# AD.net
KiCad netlist of a schematic drawn in Altium Designer
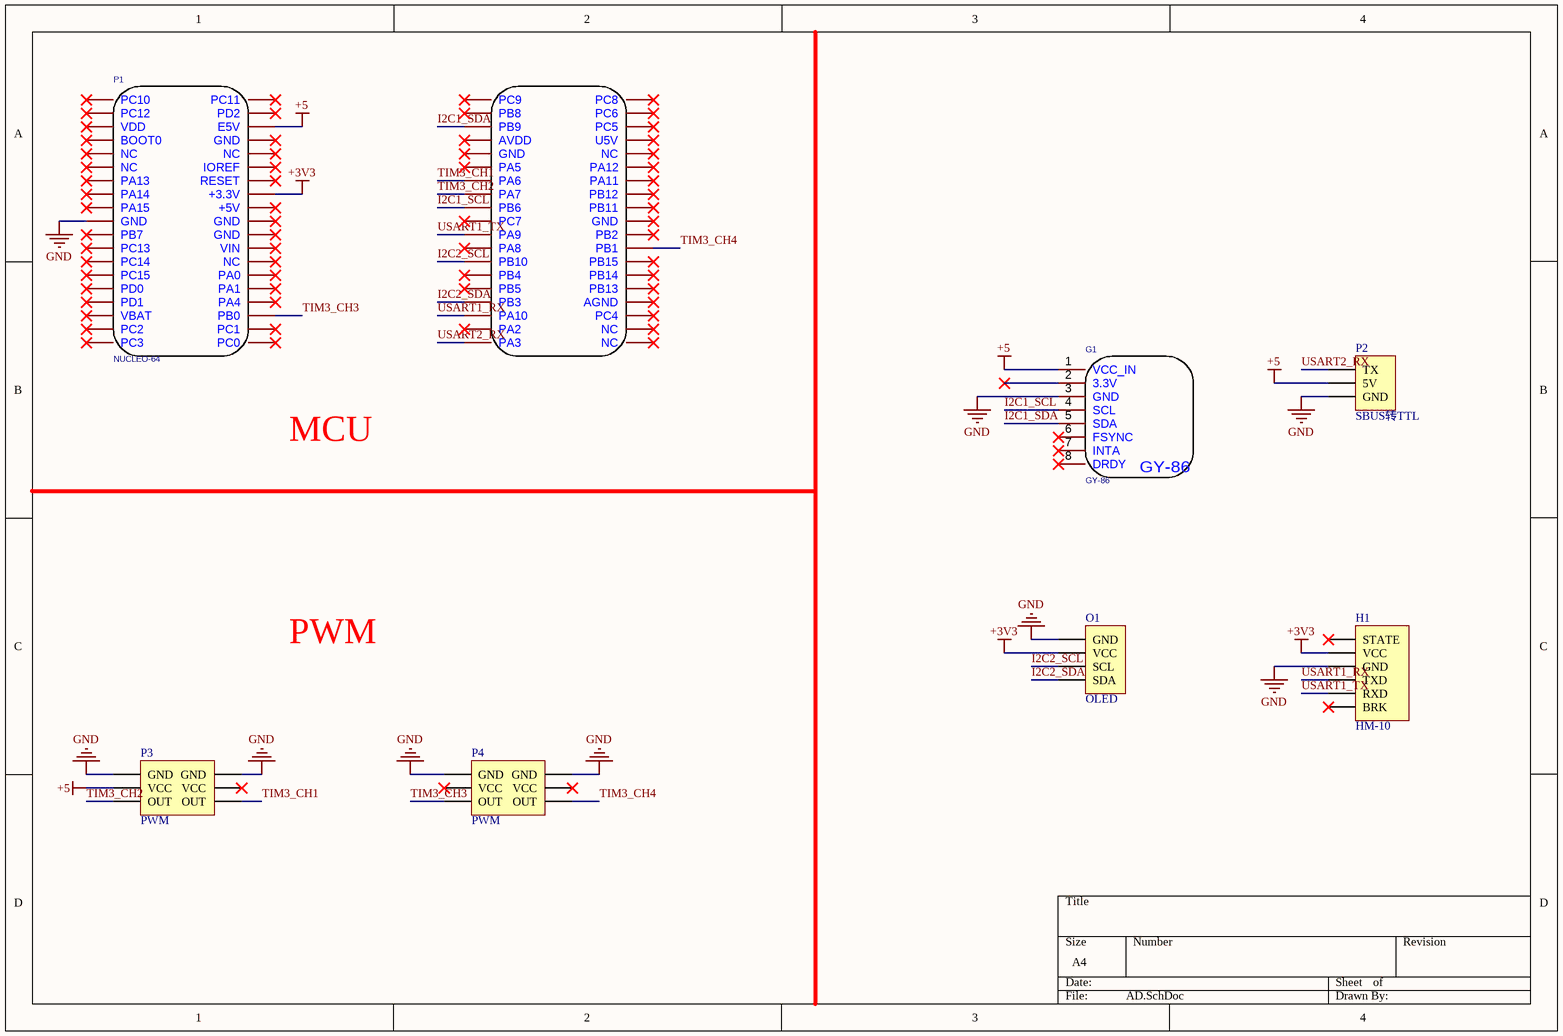
[diagram p0: AD.SchDoc]

(export (version "E")
  (design (tool "Eeschema 10.0.6"))
  (components
    (comp (ref "G1")
      (value "GY-86")
      (footprint "GY-86")
      (description "GY-86模块")
      (libsource (lib "AD") (part "GY-86"))
    )
    (comp (ref "H1")
      (value "HM-10")
      (footprint "HDR1X6")
      (description "HM-10蓝牙模块")
      (fields (field (name "PUBLISHER") "Altium Limited"))
      (libsource (lib "AD") (part "HM-10"))
    )
    (comp (ref "O1")
      (value "OLED")
      (footprint "HDR1X4")
      (description "使用I2C通信的0.96寸OLED模块")
      (fields (field (name "PUBLISHER") "Altium Limited"))
      (libsource (lib "AD") (part "OLED"))
    )
    (comp (ref "P1")
      (value "NUCLEO-64")
      (footprint "NUCLEO-F103RB")
      (description "STM32F401NUCLEO开发板")
      (fields (field (name "MANUFACTURER") "ST"))
      (libsource (lib "AD") (part "NUCLEO-64"))
    )
    (comp (ref "P2")
      (value "SBUS转TTL")
      (footprint "HDR1X3")
      (description "SBUS转TTL模块")
      (fields (field (name "PUBLISHER") "Altium Limited"))
      (libsource (lib "AD") (part "SBUS转TTL"))
    )
    (comp (ref "P3")
      (value "PWM")
      (footprint "HDR2.54-WI-2x3P")
      (description "电机PWM输出")
      (fields (field (name "PUBLISHER") "Altium Limited"))
      (libsource (lib "AD") (part "PWM"))
    )
    (comp (ref "P4")
      (value "PWM")
      (footprint "HDR2.54-WI-2x3P")
      (description "电机PWM输出")
      (fields (field (name "PUBLISHER") "Altium Limited"))
      (libsource (lib "AD") (part "PWM"))
    )
  )
  (nets
    (net (code "1") (name "+3V3") (class "Default")
      (node (ref "H1") (pin "2") (pinfunction "VCC_2") (pintype "passive"))
      (node (ref "O1") (pin "2") (pinfunction "VCC_2") (pintype "passive"))
      (node (ref "P1") (pin "16") (pinfunction "+3.3V_16") (pintype "passive"))
    )
    (net (code "2") (name "+5") (class "Default")
      (node (ref "G1") (pin "1") (pinfunction "VCC_IN_1") (pintype "passive"))
      (node (ref "P1") (pin "6") (pinfunction "E5V_6") (pintype "passive"))
      (node (ref "P2") (pin "2") (pinfunction "5V_2") (pintype "passive"))
      (node (ref "P3") (pin "3") (pinfunction "VCC_3") (pintype "passive"))
    )
    (net (code "3") (name "/I2C1_SCL") (class "Default")
      (node (ref "G1") (pin "4") (pinfunction "SCL_4") (pintype "passive"))
      (node (ref "P1") (pin "89") (pinfunction "PB6_89") (pintype "passive"))
    )
    (net (code "4") (name "/I2C1_SDA") (class "Default")
      (node (ref "G1") (pin "5") (pinfunction "SDA_5") (pintype "passive"))
      (node (ref "P1") (pin "77") (pinfunction "PB9_77") (pintype "passive"))
    )
    (net (code "5") (name "/I2C2_SCL") (class "Default")
      (node (ref "O1") (pin "3") (pinfunction "SCL_3") (pintype "passive"))
      (node (ref "P1") (pin "97") (pinfunction "PB10_97") (pintype "passive"))
    )
    (net (code "6") (name "/I2C2_SDA") (class "Default")
      (node (ref "O1") (pin "4") (pinfunction "SDA_4") (pintype "passive"))
      (node (ref "P1") (pin "103") (pinfunction "PB3_103") (pintype "passive"))
    )
    (net (code "7") (name "/TIM3_CH1") (class "Default")
      (node (ref "P1") (pin "85") (pinfunction "PA6_85") (pintype "passive"))
      (node (ref "P3") (pin "6") (pinfunction "OUT_6") (pintype "passive"))
    )
    (net (code "8") (name "/TIM3_CH2") (class "Default")
      (node (ref "P1") (pin "87") (pinfunction "PA7_87") (pintype "passive"))
      (node (ref "P3") (pin "5") (pinfunction "OUT_5") (pintype "passive"))
    )
    (net (code "9") (name "/TIM3_CH3") (class "Default")
      (node (ref "P1") (pin "34") (pinfunction "PB0_34") (pintype "passive"))
      (node (ref "P4") (pin "5") (pinfunction "OUT_5") (pintype "passive"))
    )
    (net (code "10") (name "/TIM3_CH4") (class "Default")
      (node (ref "P1") (pin "96") (pinfunction "PB1_96") (pintype "passive"))
      (node (ref "P4") (pin "6") (pinfunction "OUT_6") (pintype "passive"))
    )
    (net (code "11") (name "/USART1_RX") (class "Default")
      (node (ref "H1") (pin "4") (pinfunction "TXD_4") (pintype "passive"))
      (node (ref "P1") (pin "105") (pinfunction "PA10_105") (pintype "passive"))
    )
    (net (code "12") (name "/USART1_TX") (class "Default")
      (node (ref "H1") (pin "5") (pinfunction "RXD_5") (pintype "passive"))
      (node (ref "P1") (pin "93") (pinfunction "PA9_93") (pintype "passive"))
    )
    (net (code "13") (name "/USART2_RX") (class "Default")
      (node (ref "P1") (pin "109") (pinfunction "PA3_109") (pintype "passive"))
      (node (ref "P2") (pin "1") (pinfunction "TX_1") (pintype "passive"))
    )
    (net (code "14") (name "GND") (class "Default")
      (node (ref "G1") (pin "3") (pinfunction "GND_3") (pintype "passive"))
      (node (ref "H1") (pin "3") (pinfunction "GND_3") (pintype "passive"))
      (node (ref "O1") (pin "1") (pinfunction "GND_1") (pintype "passive"))
      (node (ref "P1") (pin "19") (pinfunction "GND_19") (pintype "passive"))
      (node (ref "P2") (pin "3") (pinfunction "GND_3") (pintype "passive"))
      (node (ref "P3") (pin "1") (pinfunction "GND_1") (pintype "passive"))
      (node (ref "P3") (pin "2") (pinfunction "GND_2") (pintype "passive"))
      (node (ref "P4") (pin "1") (pinfunction "GND_1") (pintype "passive"))
      (node (ref "P4") (pin "2") (pinfunction "GND_2") (pintype "passive"))
    )
    (net (code "15") (name "unconnected-(G1-3.3V-Pad2)") (class "Default")
      (node (ref "G1") (pin "2") (pinfunction "3.3V_2") (pintype "passive+no_connect"))
    )
    (net (code "16") (name "unconnected-(G1-DRDY-Pad8)") (class "Default")
      (node (ref "G1") (pin "8") (pinfunction "DRDY_8") (pintype "passive+no_connect"))
    )
    (net (code "17") (name "unconnected-(G1-FSYNC-Pad6)") (class "Default")
      (node (ref "G1") (pin "6") (pinfunction "FSYNC_6") (pintype "passive+no_connect"))
    )
    (net (code "18") (name "unconnected-(G1-INTA-Pad7)") (class "Default")
      (node (ref "G1") (pin "7") (pinfunction "INTA_7") (pintype "passive+no_connect"))
    )
    (net (code "19") (name "unconnected-(H1-BRK-Pad6)") (class "Default")
      (node (ref "H1") (pin "6") (pinfunction "BRK_6") (pintype "passive+no_connect"))
    )
    (net (code "20") (name "unconnected-(H1-STATE-Pad1)") (class "Default")
      (node (ref "H1") (pin "1") (pinfunction "STATE_1") (pintype "passive+no_connect"))
    )
    (net (code "21") (name "unconnected-(P1-+5V-Pad18)") (class "Default")
      (node (ref "P1") (pin "18") (pinfunction "+5V_18") (pintype "passive+no_connect"))
    )
    (net (code "22") (name "unconnected-(P1-AGND-Pad104)") (class "Default")
      (node (ref "P1") (pin "104") (pinfunction "AGND_104") (pintype "passive+no_connect"))
    )
    (net (code "23") (name "unconnected-(P1-AVDD-Pad79)") (class "Default")
      (node (ref "P1") (pin "79") (pinfunction "AVDD_79") (pintype "passive+no_connect"))
    )
    (net (code "24") (name "unconnected-(P1-BOOT0-Pad7)") (class "Default")
      (node (ref "P1") (pin "7") (pinfunction "BOOT0_7") (pintype "passive+no_connect"))
    )
    (net (code "25") (name "unconnected-(P1-GND-Pad8)") (class "Default")
      (node (ref "P1") (pin "8") (pinfunction "GND_8") (pintype "passive+no_connect"))
    )
    (net (code "26") (name "unconnected-(P1-GND-Pad20)") (class "Default")
      (node (ref "P1") (pin "20") (pinfunction "GND_20") (pintype "passive+no_connect"))
    )
    (net (code "27") (name "unconnected-(P1-GND-Pad22)") (class "Default")
      (node (ref "P1") (pin "22") (pinfunction "GND_22") (pintype "passive+no_connect"))
    )
    (net (code "28") (name "unconnected-(P1-GND-Pad81)") (class "Default")
      (node (ref "P1") (pin "81") (pinfunction "GND_81") (pintype "passive+no_connect"))
    )
    (net (code "29") (name "unconnected-(P1-GND-Pad92)") (class "Default")
      (node (ref "P1") (pin "92") (pinfunction "GND_92") (pintype "passive+no_connect"))
    )
    (net (code "30") (name "unconnected-(P1-IOREF-Pad12)") (class "Default")
      (node (ref "P1") (pin "12") (pinfunction "IOREF_12") (pintype "passive+no_connect"))
    )
    (net (code "31") (name "unconnected-(P1-NC-Pad9)") (class "Default")
      (node (ref "P1") (pin "9") (pinfunction "NC_9") (pintype "passive+no_connect"))
    )
    (net (code "32") (name "unconnected-(P1-NC-Pad10)") (class "Default")
      (node (ref "P1") (pin "10") (pinfunction "NC_10") (pintype "passive+no_connect"))
    )
    (net (code "33") (name "unconnected-(P1-NC-Pad11)") (class "Default")
      (node (ref "P1") (pin "11") (pinfunction "NC_11") (pintype "passive+no_connect"))
    )
    (net (code "34") (name "unconnected-(P1-NC-Pad26)") (class "Default")
      (node (ref "P1") (pin "26") (pinfunction "NC_26") (pintype "passive+no_connect"))
    )
    (net (code "35") (name "unconnected-(P1-NC-Pad82)") (class "Default")
      (node (ref "P1") (pin "82") (pinfunction "NC_82") (pintype "passive+no_connect"))
    )
    (net (code "36") (name "unconnected-(P1-NC-Pad108)") (class "Default")
      (node (ref "P1") (pin "108") (pinfunction "NC_108") (pintype "passive+no_connect"))
    )
    (net (code "37") (name "unconnected-(P1-NC-Pad110)") (class "Default")
      (node (ref "P1") (pin "110") (pinfunction "NC_110") (pintype "passive+no_connect"))
    )
    (net (code "38") (name "unconnected-(P1-PA0-Pad28)") (class "Default")
      (node (ref "P1") (pin "28") (pinfunction "PA0_28") (pintype "passive+no_connect"))
    )
    (net (code "39") (name "unconnected-(P1-PA1-Pad30)") (class "Default")
      (node (ref "P1") (pin "30") (pinfunction "PA1_30") (pintype "passive+no_connect"))
    )
    (net (code "40") (name "unconnected-(P1-PA2-Pad107)") (class "Default")
      (node (ref "P1") (pin "107") (pinfunction "PA2_107") (pintype "passive+no_connect"))
    )
    (net (code "41") (name "unconnected-(P1-PA4-Pad32)") (class "Default")
      (node (ref "P1") (pin "32") (pinfunction "PA4_32") (pintype "passive+no_connect"))
    )
    (net (code "42") (name "unconnected-(P1-PA5-Pad83)") (class "Default")
      (node (ref "P1") (pin "83") (pinfunction "PA5_83") (pintype "passive+no_connect"))
    )
    (net (code "43") (name "unconnected-(P1-PA8-Pad95)") (class "Default")
      (node (ref "P1") (pin "95") (pinfunction "PA8_95") (pintype "passive+no_connect"))
    )
    (net (code "44") (name "unconnected-(P1-PA11-Pad86)") (class "Default")
      (node (ref "P1") (pin "86") (pinfunction "PA11_86") (pintype "passive+no_connect"))
    )
    (net (code "45") (name "unconnected-(P1-PA12-Pad84)") (class "Default")
      (node (ref "P1") (pin "84") (pinfunction "PA12_84") (pintype "passive+no_connect"))
    )
    (net (code "46") (name "unconnected-(P1-PA13-Pad13)") (class "Default")
      (node (ref "P1") (pin "13") (pinfunction "PA13_13") (pintype "passive+no_connect"))
    )
    (net (code "47") (name "unconnected-(P1-PA14-Pad15)") (class "Default")
      (node (ref "P1") (pin "15") (pinfunction "PA14_15") (pintype "passive+no_connect"))
    )
    (net (code "48") (name "unconnected-(P1-PA15-Pad17)") (class "Default")
      (node (ref "P1") (pin "17") (pinfunction "PA15_17") (pintype "passive+no_connect"))
    )
    (net (code "49") (name "unconnected-(P1-PB2-Pad94)") (class "Default")
      (node (ref "P1") (pin "94") (pinfunction "PB2_94") (pintype "passive+no_connect"))
    )
    (net (code "50") (name "unconnected-(P1-PB4-Pad99)") (class "Default")
      (node (ref "P1") (pin "99") (pinfunction "PB4_99") (pintype "passive+no_connect"))
    )
    (net (code "51") (name "unconnected-(P1-PB5-Pad101)") (class "Default")
      (node (ref "P1") (pin "101") (pinfunction "PB5_101") (pintype "passive+no_connect"))
    )
    (net (code "52") (name "unconnected-(P1-PB7-Pad21)") (class "Default")
      (node (ref "P1") (pin "21") (pinfunction "PB7_21") (pintype "passive+no_connect"))
    )
    (net (code "53") (name "unconnected-(P1-PB8-Pad75)") (class "Default")
      (node (ref "P1") (pin "75") (pinfunction "PB8_75") (pintype "passive+no_connect"))
    )
    (net (code "54") (name "unconnected-(P1-PB11-Pad90)") (class "Default")
      (node (ref "P1") (pin "90") (pinfunction "PB11_90") (pintype "passive+no_connect"))
    )
    (net (code "55") (name "unconnected-(P1-PB12-Pad88)") (class "Default")
      (node (ref "P1") (pin "88") (pinfunction "PB12_88") (pintype "passive+no_connect"))
    )
    (net (code "56") (name "unconnected-(P1-PB13-Pad102)") (class "Default")
      (node (ref "P1") (pin "102") (pinfunction "PB13_102") (pintype "passive+no_connect"))
    )
    (net (code "57") (name "unconnected-(P1-PB14-Pad100)") (class "Default")
      (node (ref "P1") (pin "100") (pinfunction "PB14_100") (pintype "passive+no_connect"))
    )
    (net (code "58") (name "unconnected-(P1-PB15-Pad98)") (class "Default")
      (node (ref "P1") (pin "98") (pinfunction "PB15_98") (pintype "passive+no_connect"))
    )
    (net (code "59") (name "unconnected-(P1-PC0-Pad38)") (class "Default")
      (node (ref "P1") (pin "38") (pinfunction "PC0_38") (pintype "passive+no_connect"))
    )
    (net (code "60") (name "unconnected-(P1-PC1-Pad36)") (class "Default")
      (node (ref "P1") (pin "36") (pinfunction "PC1_36") (pintype "passive+no_connect"))
    )
    (net (code "61") (name "unconnected-(P1-PC2-Pad35)") (class "Default")
      (node (ref "P1") (pin "35") (pinfunction "PC2_35") (pintype "passive+no_connect"))
    )
    (net (code "62") (name "unconnected-(P1-PC3-Pad37)") (class "Default")
      (node (ref "P1") (pin "37") (pinfunction "PC3_37") (pintype "passive+no_connect"))
    )
    (net (code "63") (name "unconnected-(P1-PC4-Pad106)") (class "Default")
      (node (ref "P1") (pin "106") (pinfunction "PC4_106") (pintype "passive+no_connect"))
    )
    (net (code "64") (name "unconnected-(P1-PC5-Pad78)") (class "Default")
      (node (ref "P1") (pin "78") (pinfunction "PC5_78") (pintype "passive+no_connect"))
    )
    (net (code "65") (name "unconnected-(P1-PC6-Pad76)") (class "Default")
      (node (ref "P1") (pin "76") (pinfunction "PC6_76") (pintype "passive+no_connect"))
    )
    (net (code "66") (name "unconnected-(P1-PC7-Pad91)") (class "Default")
      (node (ref "P1") (pin "91") (pinfunction "PC7_91") (pintype "passive+no_connect"))
    )
    (net (code "67") (name "unconnected-(P1-PC8-Pad74)") (class "Default")
      (node (ref "P1") (pin "74") (pinfunction "PC8_74") (pintype "passive+no_connect"))
    )
    (net (code "68") (name "unconnected-(P1-PC9-Pad73)") (class "Default")
      (node (ref "P1") (pin "73") (pinfunction "PC9_73") (pintype "passive+no_connect"))
    )
    (net (code "69") (name "unconnected-(P1-PC10-Pad1)") (class "Default")
      (node (ref "P1") (pin "1") (pinfunction "PC10_1") (pintype "passive+no_connect"))
    )
    (net (code "70") (name "unconnected-(P1-PC11-Pad2)") (class "Default")
      (node (ref "P1") (pin "2") (pinfunction "PC11_2") (pintype "passive+no_connect"))
    )
    (net (code "71") (name "unconnected-(P1-PC12-Pad3)") (class "Default")
      (node (ref "P1") (pin "3") (pinfunction "PC12_3") (pintype "passive+no_connect"))
    )
    (net (code "72") (name "unconnected-(P1-PC13-Pad23)") (class "Default")
      (node (ref "P1") (pin "23") (pinfunction "PC13_23") (pintype "passive+no_connect"))
    )
    (net (code "73") (name "unconnected-(P1-PC14-Pad25)") (class "Default")
      (node (ref "P1") (pin "25") (pinfunction "PC14_25") (pintype "passive+no_connect"))
    )
    (net (code "74") (name "unconnected-(P1-PC15-Pad27)") (class "Default")
      (node (ref "P1") (pin "27") (pinfunction "PC15_27") (pintype "passive+no_connect"))
    )
    (net (code "75") (name "unconnected-(P1-PD0-Pad29)") (class "Default")
      (node (ref "P1") (pin "29") (pinfunction "PD0_29") (pintype "passive+no_connect"))
    )
    (net (code "76") (name "unconnected-(P1-PD1-Pad31)") (class "Default")
      (node (ref "P1") (pin "31") (pinfunction "PD1_31") (pintype "passive+no_connect"))
    )
    (net (code "77") (name "unconnected-(P1-PD2-Pad4)") (class "Default")
      (node (ref "P1") (pin "4") (pinfunction "PD2_4") (pintype "passive+no_connect"))
    )
    (net (code "78") (name "unconnected-(P1-RESET-Pad14)") (class "Default")
      (node (ref "P1") (pin "14") (pinfunction "RESET_14") (pintype "passive+no_connect"))
    )
    (net (code "79") (name "unconnected-(P1-U5V-Pad80)") (class "Default")
      (node (ref "P1") (pin "80") (pinfunction "U5V_80") (pintype "passive+no_connect"))
    )
    (net (code "80") (name "unconnected-(P1-VBAT-Pad33)") (class "Default")
      (node (ref "P1") (pin "33") (pinfunction "VBAT_33") (pintype "passive+no_connect"))
    )
    (net (code "81") (name "unconnected-(P1-VDD-Pad5)") (class "Default")
      (node (ref "P1") (pin "5") (pinfunction "VDD_5") (pintype "passive+no_connect"))
    )
    (net (code "82") (name "unconnected-(P1-VIN-Pad24)") (class "Default")
      (node (ref "P1") (pin "24") (pinfunction "VIN_24") (pintype "passive+no_connect"))
    )
    (net (code "83") (name "unconnected-(P3-VCC-Pad4)") (class "Default")
      (node (ref "P3") (pin "4") (pinfunction "VCC_4") (pintype "passive+no_connect"))
    )
    (net (code "84") (name "unconnected-(P4-VCC-Pad3)") (class "Default")
      (node (ref "P4") (pin "3") (pinfunction "VCC_3") (pintype "passive+no_connect"))
    )
    (net (code "85") (name "unconnected-(P4-VCC-Pad4)") (class "Default")
      (node (ref "P4") (pin "4") (pinfunction "VCC_4") (pintype "passive+no_connect"))
    )
  )
)
